# Carrier_Board.net
KiCad netlist of a schematic drawn in Altium Designer
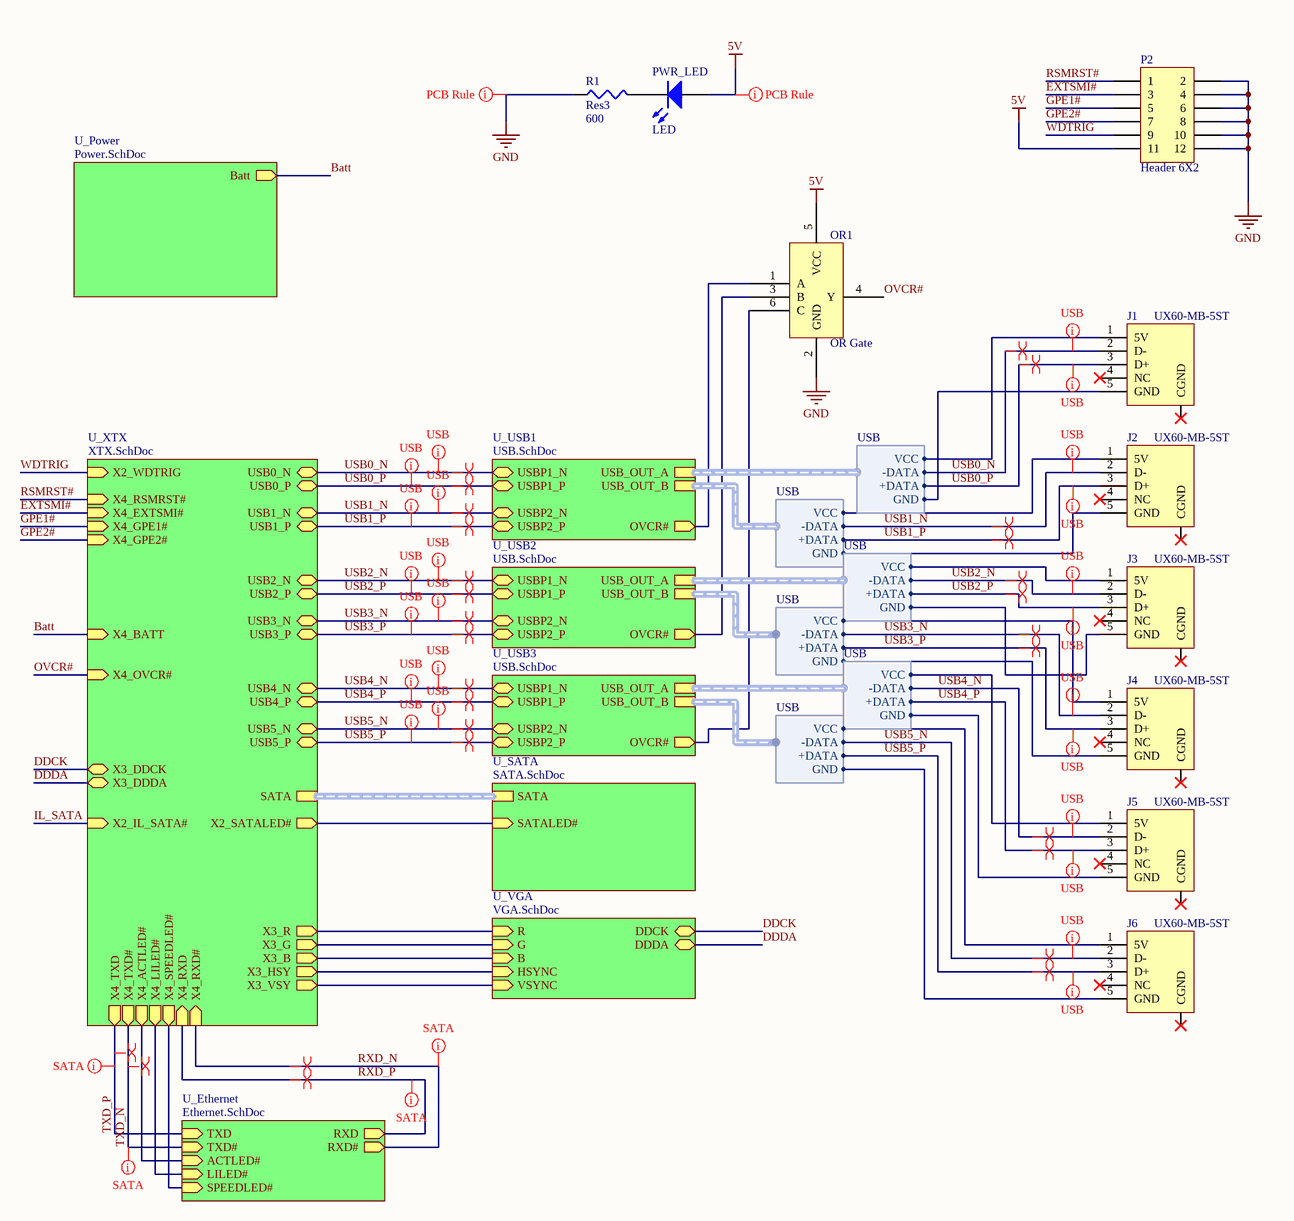
[diagram p0: Carrier_Board.SchDoc]

(export (version "E")
  (design (tool "Eeschema 10.0.6"))
  (components
    (comp (ref "J1")
      (value "UX60-MB-5ST")
      (footprint "UX60-MB-5ST")
      (description "miniUSB Type B SMT Connector")
      (libsource (lib "Hirose") (part "UX60-MB-5ST"))
    )
    (comp (ref "J2")
      (value "UX60-MB-5ST")
      (footprint "UX60-MB-5ST")
      (description "miniUSB Type B SMT Connector")
      (libsource (lib "Hirose") (part "UX60-MB-5ST"))
    )
    (comp (ref "J3")
      (value "UX60-MB-5ST")
      (footprint "UX60-MB-5ST")
      (description "miniUSB Type B SMT Connector")
      (libsource (lib "Hirose") (part "UX60-MB-5ST"))
    )
    (comp (ref "J4")
      (value "UX60-MB-5ST")
      (footprint "UX60-MB-5ST")
      (description "miniUSB Type B SMT Connector")
      (libsource (lib "Hirose") (part "UX60-MB-5ST"))
    )
    (comp (ref "J5")
      (value "UX60-MB-5ST")
      (footprint "UX60-MB-5ST")
      (description "miniUSB Type B SMT Connector")
      (libsource (lib "Hirose") (part "UX60-MB-5ST"))
    )
    (comp (ref "J6")
      (value "UX60-MB-5ST")
      (footprint "UX60-MB-5ST")
      (description "miniUSB Type B SMT Connector")
      (libsource (lib "Hirose") (part "UX60-MB-5ST"))
    )
    (comp (ref "OR1")
      (value "OR Gate")
      (footprint "TSOP65P210X110-6N")
      (description "3 Input OR Gate")
      (libsource (lib "OR Gate") (part "OR Gate"))
    )
    (comp (ref "P2")
      (value "Header 6X2")
      (footprint "HDR2X6")
      (description "Header, 6-Pin, Dual row")
      (fields (field (name "PUBLISHER") "Altium Limited"))
      (libsource (lib "Miscellaneous Connectors") (part "Header 6X2"))
    )
    (comp (ref "PWR_LED")
      (value "LED")
      (footprint "0805")
      (description "Typical RED GaAs LED")
      (fields (field (name "PUBLISHER") "Altium Limited"))
      (libsource (lib "Miscellaneous Devices") (part "LED1"))
    )
    (comp (ref "R1")
      (value "Res3")
      (footprint "J1-0603")
      (description "Resistor")
      (fields (field (name "ALTIUM_VALUE") "600") (field (name "PUBLISHER") "Altium Limited"))
      (libsource (lib "Miscellaneous Devices") (part "Res3"))
    )
  )
  (nets
    (net (code "5") (name "/EXTSMI#") (class "Default")
      (node (ref "P2") (pin "3") (pinfunction "3_3") (pintype "passive"))
    )
    (net (code "6") (name "/GPE1#") (class "Default")
      (node (ref "P2") (pin "5") (pinfunction "5_5") (pintype "passive"))
    )
    (net (code "7") (name "/GPE2#") (class "Default")
      (node (ref "P2") (pin "7") (pinfunction "7_7") (pintype "passive"))
    )
    (net (code "9") (name "/OVCR#") (class "Default")
      (node (ref "OR1") (pin "4") (pinfunction "Y_4") (pintype "passive"))
    )
    (net (code "10") (name "/OVCR#_1") (class "Default")
      (node (ref "OR1") (pin "1") (pinfunction "A_1") (pintype "passive"))
    )
    (net (code "11") (name "/OVCR#_2") (class "Default")
      (node (ref "OR1") (pin "3") (pinfunction "B_3") (pintype "passive"))
    )
    (net (code "12") (name "/OVCR#_3") (class "Default")
      (node (ref "OR1") (pin "6") (pinfunction "C_6") (pintype "passive"))
    )
    (net (code "13") (name "/RSMRST#") (class "Default")
      (node (ref "P2") (pin "1") (pinfunction "1_1") (pintype "passive"))
    )
    (net (code "19") (name "/USB0_N") (class "Default")
      (node (ref "J1") (pin "2") (pinfunction "D-_2") (pintype "passive"))
    )
    (net (code "20") (name "/USB0_P") (class "Default")
      (node (ref "J1") (pin "3") (pinfunction "D+_3") (pintype "passive"))
    )
    (net (code "21") (name "/USB1_N") (class "Default")
      (node (ref "J2") (pin "2") (pinfunction "D-_2") (pintype "passive"))
    )
    (net (code "22") (name "/USB1_P") (class "Default")
      (node (ref "J2") (pin "3") (pinfunction "D+_3") (pintype "passive"))
    )
    (net (code "23") (name "/USB2_N") (class "Default")
      (node (ref "J3") (pin "2") (pinfunction "D-_2") (pintype "passive"))
    )
    (net (code "24") (name "/USB2_P") (class "Default")
      (node (ref "J3") (pin "3") (pinfunction "D+_3") (pintype "passive"))
    )
    (net (code "25") (name "/USB3_N") (class "Default")
      (node (ref "J4") (pin "2") (pinfunction "D-_2") (pintype "passive"))
    )
    (net (code "26") (name "/USB3_P") (class "Default")
      (node (ref "J4") (pin "3") (pinfunction "D+_3") (pintype "passive"))
    )
    (net (code "27") (name "/USB4_N") (class "Default")
      (node (ref "J5") (pin "2") (pinfunction "D-_2") (pintype "passive"))
    )
    (net (code "28") (name "/USB4_P") (class "Default")
      (node (ref "J5") (pin "3") (pinfunction "D+_3") (pintype "passive"))
    )
    (net (code "29") (name "/USB5_N") (class "Default")
      (node (ref "J6") (pin "2") (pinfunction "D-_2") (pintype "passive"))
    )
    (net (code "30") (name "/USB5_P") (class "Default")
      (node (ref "J6") (pin "3") (pinfunction "D+_3") (pintype "passive"))
    )
    (net (code "31") (name "/WDTRIG") (class "Default")
      (node (ref "P2") (pin "9") (pinfunction "9_9") (pintype "passive"))
    )
    (net (code "42") (name "5V") (class "Default")
      (node (ref "OR1") (pin "5") (pinfunction "VCC_5") (pintype "passive"))
      (node (ref "P2") (pin "11") (pinfunction "11_11") (pintype "passive"))
      (node (ref "PWR_LED") (pin "1") (pinfunction "A_1") (pintype "passive"))
    )
    (net (code "43") (name "GND") (class "Default")
      (node (ref "OR1") (pin "2") (pinfunction "GND_2") (pintype "passive"))
      (node (ref "P2") (pin "10") (pinfunction "10_10") (pintype "passive"))
      (node (ref "P2") (pin "12") (pinfunction "12_12") (pintype "passive"))
      (node (ref "P2") (pin "2") (pinfunction "2_2") (pintype "passive"))
      (node (ref "P2") (pin "4") (pinfunction "4_4") (pintype "passive"))
      (node (ref "P2") (pin "6") (pinfunction "6_6") (pintype "passive"))
      (node (ref "P2") (pin "8") (pinfunction "8_8") (pintype "passive"))
      (node (ref "R1") (pin "1") (pinfunction "1_1") (pintype "passive"))
    )
    (net (code "44") (name "Net-(PWR_LED-K)") (class "Default")
      (node (ref "PWR_LED") (pin "2") (pinfunction "K_2") (pintype "passive"))
      (node (ref "R1") (pin "2") (pinfunction "2_2") (pintype "passive"))
    )
    (net (code "45") (name "unconnected-(J1-5V-Pad1)") (class "Default")
      (node (ref "J1") (pin "1") (pinfunction "5V_1") (pintype "passive"))
    )
    (net (code "46") (name "unconnected-(J1-GND-Pad5)") (class "Default")
      (node (ref "J1") (pin "5") (pinfunction "GND_5") (pintype "passive"))
    )
    (net (code "47") (name "unconnected-(J1-NC-Pad4)") (class "Default")
      (node (ref "J1") (pin "4") (pinfunction "NC_4") (pintype "passive+no_connect"))
    )
    (net (code "48") (name "unconnected-(J1-PadCGND)") (class "Default")
      (node (ref "J1") (pin "CGND") (pinfunction "CGND_CGND") (pintype "passive+no_connect"))
    )
    (net (code "49") (name "unconnected-(J2-5V-Pad1)") (class "Default")
      (node (ref "J2") (pin "1") (pinfunction "5V_1") (pintype "passive"))
    )
    (net (code "50") (name "unconnected-(J2-GND-Pad5)") (class "Default")
      (node (ref "J2") (pin "5") (pinfunction "GND_5") (pintype "passive"))
    )
    (net (code "51") (name "unconnected-(J2-NC-Pad4)") (class "Default")
      (node (ref "J2") (pin "4") (pinfunction "NC_4") (pintype "passive+no_connect"))
    )
    (net (code "52") (name "unconnected-(J2-PadCGND)") (class "Default")
      (node (ref "J2") (pin "CGND") (pinfunction "CGND_CGND") (pintype "passive+no_connect"))
    )
    (net (code "53") (name "unconnected-(J3-5V-Pad1)") (class "Default")
      (node (ref "J3") (pin "1") (pinfunction "5V_1") (pintype "passive"))
    )
    (net (code "54") (name "unconnected-(J3-GND-Pad5)") (class "Default")
      (node (ref "J3") (pin "5") (pinfunction "GND_5") (pintype "passive"))
    )
    (net (code "55") (name "unconnected-(J3-NC-Pad4)") (class "Default")
      (node (ref "J3") (pin "4") (pinfunction "NC_4") (pintype "passive+no_connect"))
    )
    (net (code "56") (name "unconnected-(J3-PadCGND)") (class "Default")
      (node (ref "J3") (pin "CGND") (pinfunction "CGND_CGND") (pintype "passive+no_connect"))
    )
    (net (code "57") (name "unconnected-(J4-5V-Pad1)") (class "Default")
      (node (ref "J4") (pin "1") (pinfunction "5V_1") (pintype "passive"))
    )
    (net (code "58") (name "unconnected-(J4-GND-Pad5)") (class "Default")
      (node (ref "J4") (pin "5") (pinfunction "GND_5") (pintype "passive"))
    )
    (net (code "59") (name "unconnected-(J4-NC-Pad4)") (class "Default")
      (node (ref "J4") (pin "4") (pinfunction "NC_4") (pintype "passive+no_connect"))
    )
    (net (code "60") (name "unconnected-(J4-PadCGND)") (class "Default")
      (node (ref "J4") (pin "CGND") (pinfunction "CGND_CGND") (pintype "passive+no_connect"))
    )
    (net (code "61") (name "unconnected-(J5-5V-Pad1)") (class "Default")
      (node (ref "J5") (pin "1") (pinfunction "5V_1") (pintype "passive"))
    )
    (net (code "62") (name "unconnected-(J5-GND-Pad5)") (class "Default")
      (node (ref "J5") (pin "5") (pinfunction "GND_5") (pintype "passive"))
    )
    (net (code "63") (name "unconnected-(J5-NC-Pad4)") (class "Default")
      (node (ref "J5") (pin "4") (pinfunction "NC_4") (pintype "passive+no_connect"))
    )
    (net (code "64") (name "unconnected-(J5-PadCGND)") (class "Default")
      (node (ref "J5") (pin "CGND") (pinfunction "CGND_CGND") (pintype "passive+no_connect"))
    )
    (net (code "65") (name "unconnected-(J6-5V-Pad1)") (class "Default")
      (node (ref "J6") (pin "1") (pinfunction "5V_1") (pintype "passive"))
    )
    (net (code "66") (name "unconnected-(J6-GND-Pad5)") (class "Default")
      (node (ref "J6") (pin "5") (pinfunction "GND_5") (pintype "passive"))
    )
    (net (code "67") (name "unconnected-(J6-NC-Pad4)") (class "Default")
      (node (ref "J6") (pin "4") (pinfunction "NC_4") (pintype "passive+no_connect"))
    )
    (net (code "68") (name "unconnected-(J6-PadCGND)") (class "Default")
      (node (ref "J6") (pin "CGND") (pinfunction "CGND_CGND") (pintype "passive+no_connect"))
    )
  )
)
